# Power_and_Control.net
KiCad netlist of a schematic drawn in Altium Designer
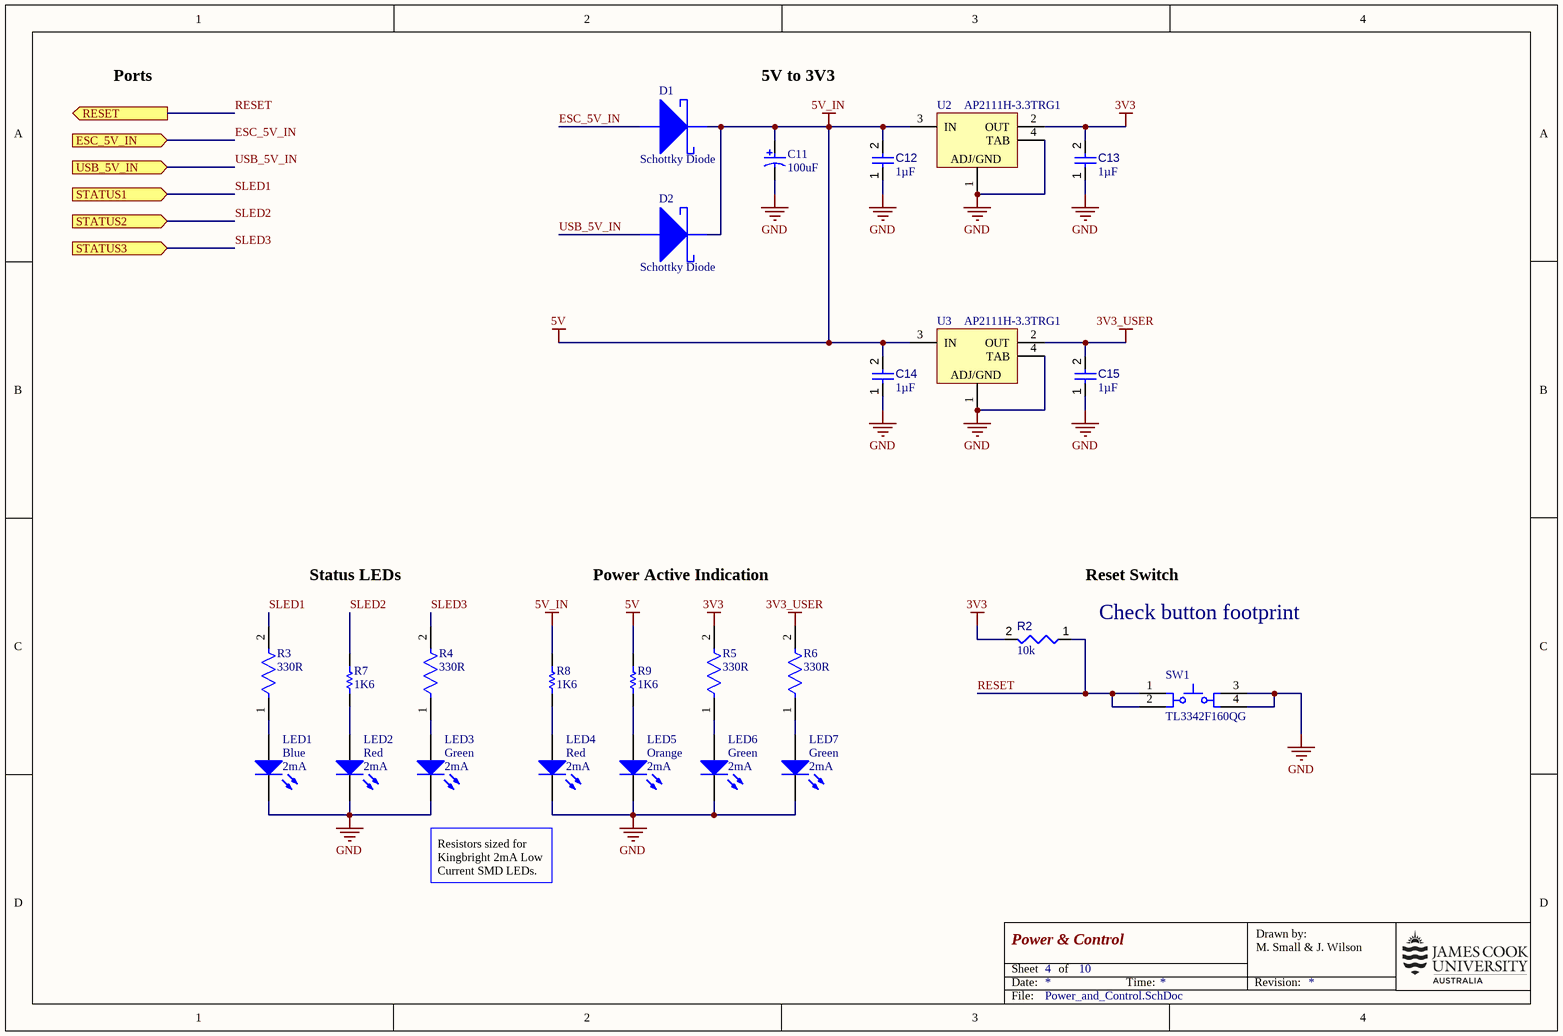
[diagram p0: Power_and_Control.SchDoc]

(export (version "E")
  (design (tool "Eeschema 10.0.6"))
  (components
    (comp (ref "C11")
      (value "100uF")
      (footprint "PNSC-FP-V-D8_V")
      (fields (field (name "MANUFACTURER") "Panasonic"))
      (libsource (lib "Altium Content Vault") (part "CAP-P-2"))
    )
    (comp (ref "C12")
      (value "1µF")
      (footprint "CAPC0805(2012)145_L")
      (description "Chip Capacitor, 1µF +/-20%, 25V, 0805, Thickness 1.45 mm")
      (fields (field (name "TOLERANCE") "10%") (field (name "Comment") "Capacitor 1µF +/-20% 25V 0805"))
      (libsource (lib "James Cook University") (part "CAP-NP-2"))
    )
    (comp (ref "C13")
      (value "1µF")
      (footprint "CAPC0805(2012)145_L")
      (description "Chip Capacitor, 1µF +/-20%, 25V, 0805, Thickness 1.45 mm")
      (fields (field (name "TOLERANCE") "10%") (field (name "Comment") "Capacitor 1µF +/-20% 25V 0805"))
      (libsource (lib "James Cook University") (part "CAP-NP-2"))
    )
    (comp (ref "C14")
      (value "1µF")
      (footprint "CAPC0805(2012)145_L")
      (description "Chip Capacitor, 1µF +/-20%, 25V, 0805, Thickness 1.45 mm")
      (fields (field (name "TOLERANCE") "10%") (field (name "Comment") "Capacitor 1µF +/-20% 25V 0805"))
      (libsource (lib "James Cook University") (part "CAP-NP-2"))
    )
    (comp (ref "C15")
      (value "1µF")
      (footprint "CAPC0805(2012)145_L")
      (description "Chip Capacitor, 1µF +/-20%, 25V, 0805, Thickness 1.45 mm")
      (fields (field (name "TOLERANCE") "10%") (field (name "Comment") "Capacitor 1µF +/-20% 25V 0805"))
      (libsource (lib "James Cook University") (part "CAP-NP-2"))
    )
    (comp (ref "D1")
      (value "Schottky Diode")
      (footprint "DO-221BC")
      (description "Small Signal Schottky Diode, Single, 45 V, 8 A, 570 mV")
      (libsource (lib "CC2511_Library_MS") (part "Schottky 2 pin 8A"))
    )
    (comp (ref "D2")
      (value "Schottky Diode")
      (footprint "DO-221BC")
      (description "Small Signal Schottky Diode, Single, 45 V, 8 A, 570 mV")
      (libsource (lib "CC2511_Library_MS") (part "Schottky 2 pin 8A"))
    )
    (comp (ref "LED1")
      (value "Blue")
      (footprint "1206_A")
      (description "KPT-3216LVVBC-D -  LED, 3.2mm x 1.6mm, Blue, SMD, 2 mA, 2.65 V, 470 nm")
      (fields
        (field (name "MANUFACTURER") "Kingbright")
        (field (name "PARTNUMBER") "KPT-3216LVVBC-D")
        (field (name "IF") "2mA")
      )
      (libsource (lib "Altium Content Vault") (part "CMP-1426-00015-1"))
    )
    (comp (ref "LED2")
      (value "Red")
      (footprint "1206_A")
      (description "KPT-3216LVSECK-J3-PRV -  LED, 3.2mm x 1.6mm, Red, SMD, 2 mA, 1.8 V, 625 nm")
      (fields
        (field (name "PARTNUMBER") "KPT-3216LVSECK-J3-PRV")
        (field (name "MANUFACTURER") "Kingbright")
        (field (name "IF") "2mA")
      )
      (libsource (lib "Altium Content Vault") (part "CMP-1426-00013-1"))
    )
    (comp (ref "LED3")
      (value "Green")
      (footprint "1206_A")
      (description "KPT-3216LVZGCK -  LED, 3.2mm x 1.6mm, Green, SMD, 2 mA, 2.65 V, 525 nm")
      (fields
        (field (name "MANUFACTURER") "Kingbright")
        (field (name "PARTNUMBER") "KPT-3216LVZGCK")
        (field (name "IF") "2mA")
      )
      (libsource (lib "Altium Content Vault") (part "CMP-1426-00014-1"))
    )
    (comp (ref "LED4")
      (value "Red")
      (footprint "1206_A")
      (description "KPT-3216LVSECK-J3-PRV -  LED, 3.2mm x 1.6mm, Red, SMD, 2 mA, 1.8 V, 625 nm")
      (fields
        (field (name "PARTNUMBER") "KPT-3216LVSECK-J3-PRV")
        (field (name "MANUFACTURER") "Kingbright")
        (field (name "IF") "2mA")
      )
      (libsource (lib "Altium Content Vault") (part "CMP-1426-00013-1"))
    )
    (comp (ref "LED5")
      (value "Orange")
      (footprint "1206_A")
      (description "APT3216LSECK/J4-PRV -  LED, 3.2mm x 1.6mm, Orange, SMD, 2 mA, 1.8 V, 590 nm")
      (fields
        (field (name "PARTNUMBER") "KPT-3216LVSYCK-J3-PRV")
        (field (name "MANUFACTURER") "Kingbright")
        (field (name "IF") "2mA")
      )
      (libsource (lib "Altium Content Vault") (part "CMP-1426-00019-1"))
    )
    (comp (ref "LED6")
      (value "Green")
      (footprint "1206_A")
      (description "KPT-3216LVZGCK -  LED, 3.2mm x 1.6mm, Green, SMD, 2 mA, 2.65 V, 525 nm")
      (fields
        (field (name "MANUFACTURER") "Kingbright")
        (field (name "PARTNUMBER") "KPT-3216LVZGCK")
        (field (name "IF") "2mA")
      )
      (libsource (lib "Altium Content Vault") (part "CMP-1426-00014-1"))
    )
    (comp (ref "LED7")
      (value "Green")
      (footprint "1206_A")
      (description "KPT-3216LVZGCK -  LED, 3.2mm x 1.6mm, Green, SMD, 2 mA, 2.65 V, 525 nm")
      (fields
        (field (name "MANUFACTURER") "Kingbright")
        (field (name "PARTNUMBER") "KPT-3216LVZGCK")
        (field (name "IF") "2mA")
      )
      (libsource (lib "Altium Content Vault") (part "CMP-1426-00014-1"))
    )
    (comp (ref "R2")
      (value "10k")
      (footprint "RESC0805(2012)_L")
      (description "Chip Resistor, 10 kOhms, +/-5%, 125 mW, -55 to 155 degC, 0805")
      (fields (field (name "POWER") "125mW") (field (name "TOLERANCE") "5%"))
      (libsource (lib "James Cook University") (part "RES-2"))
    )
    (comp (ref "R3")
      (value "330R")
      (footprint "FP-CRCW0805-e3-MFG")
      (description "RES Thick Film, 330Ω, 1%, 0.125W, 100ppm/°C, 0805")
      (fields (field (name "TOLERANCE") "1%"))
      (libsource (lib "Altium Content Vault") (part "1029c3af85768c4190bb7ad29bc67b5"))
    )
    (comp (ref "R4")
      (value "330R")
      (footprint "FP-CRCW0805-e3-MFG")
      (description "RES Thick Film, 330Ω, 1%, 0.125W, 100ppm/°C, 0805")
      (fields (field (name "TOLERANCE") "1%"))
      (libsource (lib "Altium Content Vault") (part "1029c3af85768c4190bb7ad29bc67b5"))
    )
    (comp (ref "R5")
      (value "330R")
      (footprint "FP-CRCW0805-e3-MFG")
      (description "RES Thick Film, 330Ω, 1%, 0.125W, 100ppm/°C, 0805")
      (fields (field (name "TOLERANCE") "1%"))
      (libsource (lib "Altium Content Vault") (part "1029c3af85768c4190bb7ad29bc67b5"))
    )
    (comp (ref "R6")
      (value "330R")
      (footprint "FP-CRCW0805-e3-MFG")
      (description "RES Thick Film, 330Ω, 1%, 0.125W, 100ppm/°C, 0805")
      (fields (field (name "TOLERANCE") "1%"))
      (libsource (lib "Altium Content Vault") (part "1029c3af85768c4190bb7ad29bc67b5"))
    )
    (comp (ref "R7")
      (value "1K6")
      (footprint "RESC2013X50X30LL20T20")
      (fields (field (name "PART NUMBER") "CRCW08051K60FKEA") (field (name "MANUFACTURER") "Vishay Dale"))
      (libsource (lib "Altium Content Vault") (part "RES"))
    )
    (comp (ref "R8")
      (value "1K6")
      (footprint "RESC2013X50X30LL20T20")
      (fields (field (name "PART NUMBER") "CRCW08051K60FKEA") (field (name "MANUFACTURER") "Vishay Dale"))
      (libsource (lib "Altium Content Vault") (part "RES"))
    )
    (comp (ref "R9")
      (value "1K6")
      (footprint "RESC2013X50X30LL20T20")
      (fields (field (name "PART NUMBER") "CRCW08051K60FKEA") (field (name "MANUFACTURER") "Vishay Dale"))
      (libsource (lib "Altium Content Vault") (part "RES"))
    )
    (comp (ref "SW1")
      (value "TL3342F160QG")
      (footprint "ESWI-TL3342F160QG_V")
      (description "Tactile Switch, SPST-NO, 50 mA, 12 V, 4-Pin SMD, RoHS, Tape and Reel")
      (fields (field (name "MANUFACTURER") "E-Switch"))
      (libsource (lib "James Cook University") (part "SW-SPST-NO-4"))
    )
    (comp (ref "U2")
      (value "AP2111H-3.3TRG1")
      (footprint "ONSC-SOT-223-4-318H-01_A_V")
      (fields (field (name "MANUFACTURER") "ON Semiconductor"))
      (libsource (lib "James Cook University") (part "ONSC-NCP1117-SOT223-4"))
    )
    (comp (ref "U3")
      (value "AP2111H-3.3TRG1")
      (footprint "ONSC-SOT-223-4-318H-01_A_V")
      (fields (field (name "MANUFACTURER") "ON Semiconductor"))
      (libsource (lib "James Cook University") (part "ONSC-NCP1117-SOT223-4"))
    )
  )
  (nets
    (net (code "1") (name "/ESC_5V_IN") (class "Default")
      (node (ref "D1") (pin "2") (pinfunction "2_2") (pintype "passive"))
    )
    (net (code "2") (name "/RESET") (class "Default")
      (node (ref "R2") (pin "1") (pinfunction "1_1") (pintype "passive"))
      (node (ref "SW1") (pin "1") (pinfunction "1_1") (pintype "passive"))
      (node (ref "SW1") (pin "2") (pinfunction "2_2") (pintype "passive"))
    )
    (net (code "3") (name "/SLED1") (class "Default")
      (node (ref "R3") (pin "2") (pinfunction "2_2") (pintype "passive"))
    )
    (net (code "4") (name "/SLED2") (class "Default")
      (node (ref "R7") (pin "2") (pinfunction "2_2") (pintype "passive"))
    )
    (net (code "5") (name "/SLED3") (class "Default")
      (node (ref "R4") (pin "2") (pinfunction "2_2") (pintype "passive"))
    )
    (net (code "6") (name "/USB_5V_IN") (class "Default")
      (node (ref "D2") (pin "2") (pinfunction "2_2") (pintype "passive"))
    )
    (net (code "7") (name "3V3") (class "Default")
      (node (ref "C13") (pin "2") (pinfunction "2_2") (pintype "passive"))
      (node (ref "R2") (pin "2") (pinfunction "2_2") (pintype "passive"))
      (node (ref "R5") (pin "2") (pinfunction "2_2") (pintype "passive"))
      (node (ref "U2") (pin "2") (pinfunction "OUT_2") (pintype "power_in"))
    )
    (net (code "8") (name "3V3_USER") (class "Default")
      (node (ref "C15") (pin "2") (pinfunction "2_2") (pintype "passive"))
      (node (ref "R6") (pin "2") (pinfunction "2_2") (pintype "passive"))
      (node (ref "U3") (pin "2") (pinfunction "OUT_2") (pintype "power_in"))
    )
    (net (code "9") (name "5V") (class "Default")
      (node (ref "C11") (pin "1") (pinfunction "1_1") (pintype "passive"))
      (node (ref "C12") (pin "2") (pinfunction "2_2") (pintype "passive"))
      (node (ref "C14") (pin "2") (pinfunction "2_2") (pintype "passive"))
      (node (ref "D1") (pin "1") (pinfunction "1_1") (pintype "passive"))
      (node (ref "D2") (pin "1") (pinfunction "1_1") (pintype "passive"))
      (node (ref "R8") (pin "2") (pinfunction "2_2") (pintype "passive"))
      (node (ref "R9") (pin "2") (pinfunction "2_2") (pintype "passive"))
      (node (ref "U2") (pin "3") (pinfunction "IN_3") (pintype "power_in"))
      (node (ref "U3") (pin "3") (pinfunction "IN_3") (pintype "power_in"))
    )
    (net (code "10") (name "GND") (class "Default")
      (node (ref "C11") (pin "2") (pinfunction "2_2") (pintype "passive"))
      (node (ref "C12") (pin "1") (pinfunction "1_1") (pintype "passive"))
      (node (ref "C13") (pin "1") (pinfunction "1_1") (pintype "passive"))
      (node (ref "C14") (pin "1") (pinfunction "1_1") (pintype "passive"))
      (node (ref "C15") (pin "1") (pinfunction "1_1") (pintype "passive"))
      (node (ref "LED1") (pin "1") (pinfunction "K_1") (pintype "passive"))
      (node (ref "LED2") (pin "1") (pinfunction "K_1") (pintype "passive"))
      (node (ref "LED3") (pin "1") (pinfunction "K_1") (pintype "passive"))
      (node (ref "LED4") (pin "1") (pinfunction "K_1") (pintype "passive"))
      (node (ref "LED5") (pin "1") (pinfunction "K_1") (pintype "passive"))
      (node (ref "LED6") (pin "1") (pinfunction "K_1") (pintype "passive"))
      (node (ref "LED7") (pin "1") (pinfunction "K_1") (pintype "passive"))
      (node (ref "SW1") (pin "3") (pinfunction "3_3") (pintype "passive"))
      (node (ref "SW1") (pin "4") (pinfunction "4_4") (pintype "passive"))
      (node (ref "U2") (pin "1") (pinfunction "ADJ/GND_1") (pintype "passive"))
      (node (ref "U2") (pin "4") (pinfunction "TAB_4") (pintype "passive"))
      (node (ref "U3") (pin "1") (pinfunction "ADJ/GND_1") (pintype "passive"))
      (node (ref "U3") (pin "4") (pinfunction "TAB_4") (pintype "passive"))
    )
    (net (code "11") (name "Net-(LED1-A)") (class "Default")
      (node (ref "LED1") (pin "2") (pinfunction "A_2") (pintype "passive"))
      (node (ref "R3") (pin "1") (pinfunction "1_1") (pintype "passive"))
    )
    (net (code "12") (name "Net-(LED2-A)") (class "Default")
      (node (ref "LED2") (pin "2") (pinfunction "A_2") (pintype "passive"))
      (node (ref "R7") (pin "1") (pinfunction "1_1") (pintype "passive"))
    )
    (net (code "13") (name "Net-(LED3-A)") (class "Default")
      (node (ref "LED3") (pin "2") (pinfunction "A_2") (pintype "passive"))
      (node (ref "R4") (pin "1") (pinfunction "1_1") (pintype "passive"))
    )
    (net (code "14") (name "Net-(LED4-A)") (class "Default")
      (node (ref "LED4") (pin "2") (pinfunction "A_2") (pintype "passive"))
      (node (ref "R8") (pin "1") (pinfunction "1_1") (pintype "passive"))
    )
    (net (code "15") (name "Net-(LED5-A)") (class "Default")
      (node (ref "LED5") (pin "2") (pinfunction "A_2") (pintype "passive"))
      (node (ref "R9") (pin "1") (pinfunction "1_1") (pintype "passive"))
    )
    (net (code "16") (name "Net-(LED6-A)") (class "Default")
      (node (ref "LED6") (pin "2") (pinfunction "A_2") (pintype "passive"))
      (node (ref "R5") (pin "1") (pinfunction "1_1") (pintype "passive"))
    )
    (net (code "17") (name "Net-(LED7-A)") (class "Default")
      (node (ref "LED7") (pin "2") (pinfunction "A_2") (pintype "passive"))
      (node (ref "R6") (pin "1") (pinfunction "1_1") (pintype "passive"))
    )
  )
)
